# MainBoard_v1_2.net
KiCad netlist of a schematic drawn in EAGLE
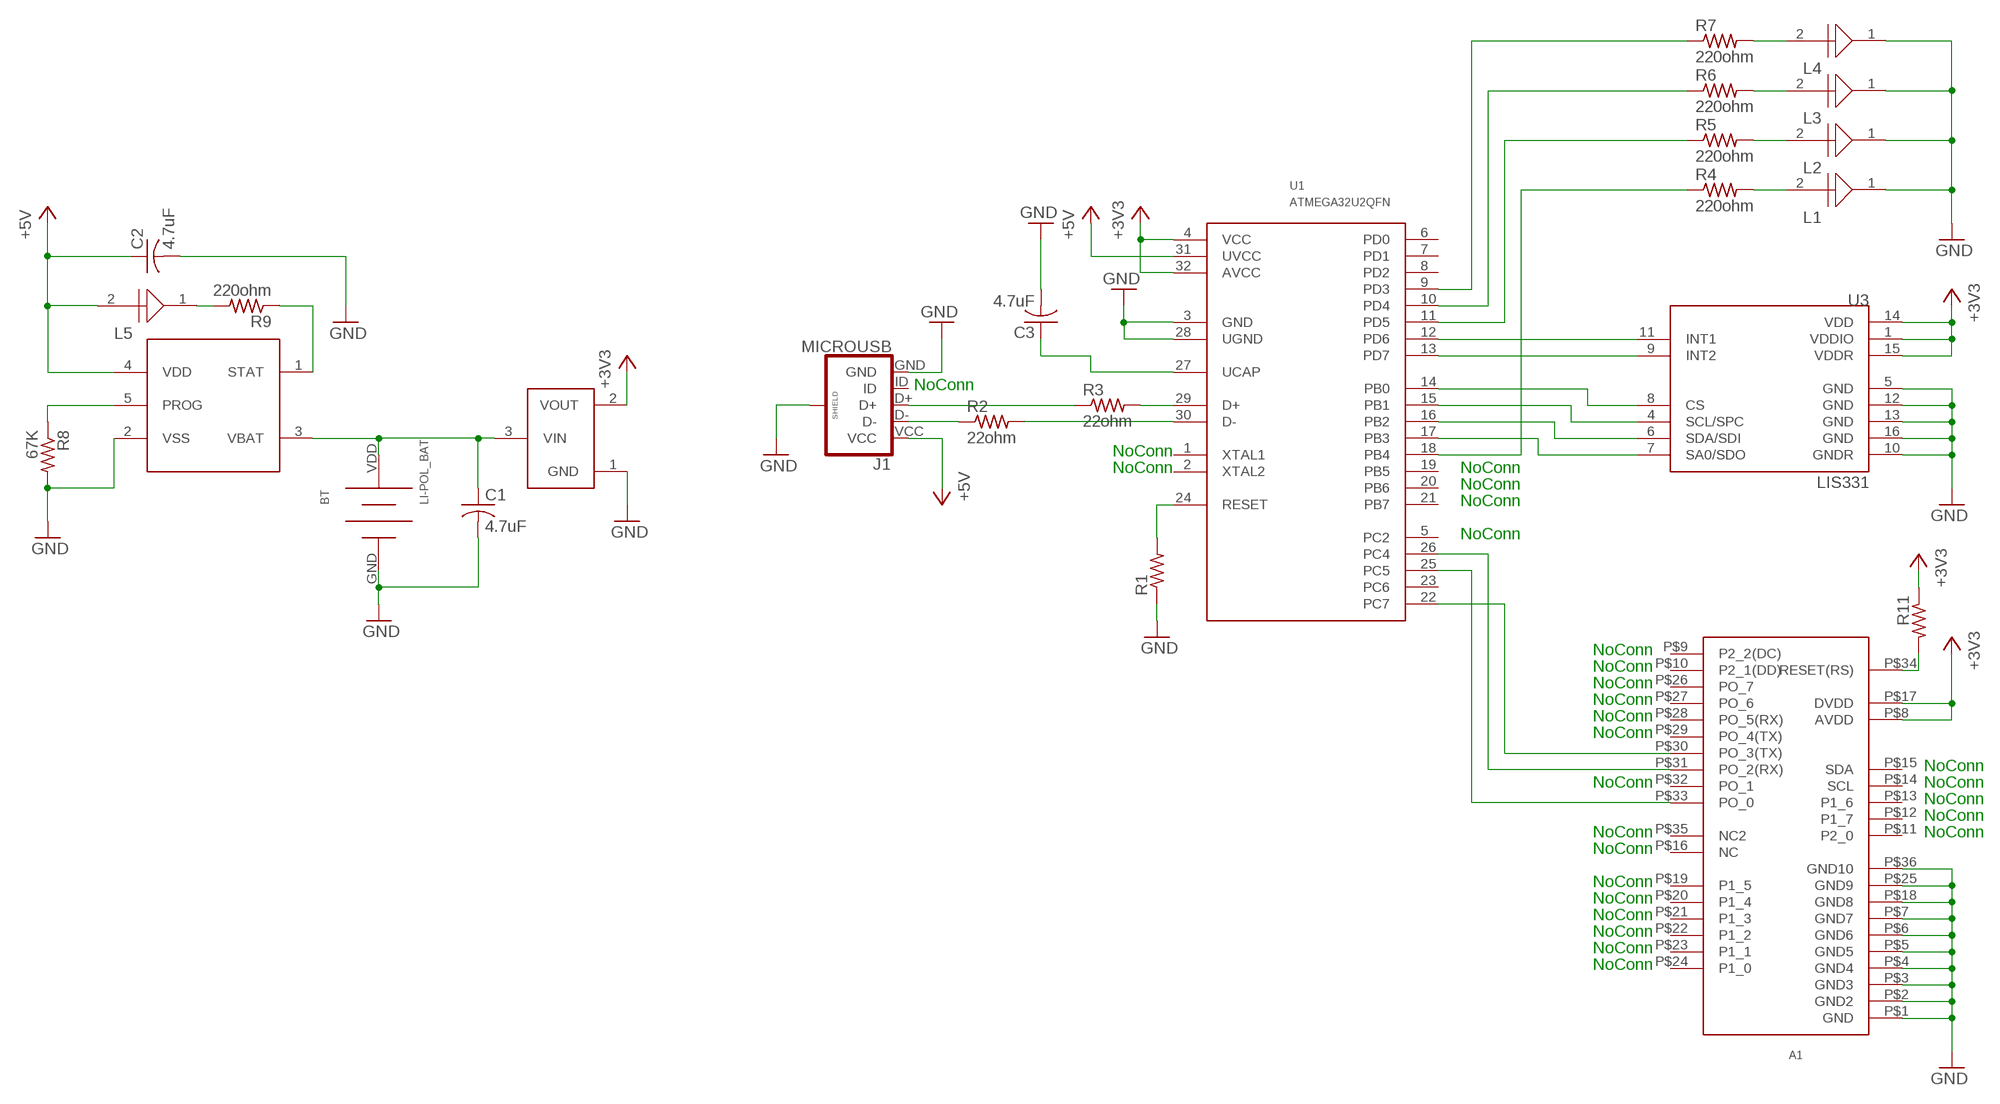
[diagram p0: schematic, sheet 1]

(export (version "E")
  (design (tool "Eeschema 10.0.6"))
  (components
    (comp (ref "A1")
      (value "BLE113-A")
      (footprint "eagle-import:BLUETOOTHNS")
      (libsource (lib "eagle-import") (part "BLE113-A"))
    )
    (comp (ref "BT")
      (value "LI-POL_BAT")
      (footprint "eagle-import:LI-POLY_28")
      (libsource (lib "eagle-import") (part "LI-POL_BAT"))
    )
    (comp (ref "C1")
      (value "4.7uF")
      (footprint "eagle-import:C0402")
      (libsource (lib "eagle-import") (part "C-USC0402"))
    )
    (comp (ref "C2")
      (value "4.7uF")
      (footprint "eagle-import:C0402")
      (libsource (lib "eagle-import") (part "C-USC0402"))
    )
    (comp (ref "C3")
      (value "4.7uF")
      (footprint "eagle-import:C0402")
      (libsource (lib "eagle-import") (part "C-USC0402"))
    )
    (comp (ref "J1")
      (value "MICROUSB")
      (footprint "eagle-import:MICROUSB")
      (libsource (lib "eagle-import") (part "MICROUSB"))
    )
    (comp (ref "L1")
      (value "LED_0402")
      (footprint "eagle-import:R0402")
      (libsource (lib "eagle-import") (part "LED_0402"))
    )
    (comp (ref "L2")
      (value "LED_0402")
      (footprint "eagle-import:R0402")
      (libsource (lib "eagle-import") (part "LED_0402"))
    )
    (comp (ref "L3")
      (value "LED_0402")
      (footprint "eagle-import:R0402")
      (libsource (lib "eagle-import") (part "LED_0402"))
    )
    (comp (ref "L4")
      (value "LED_0402")
      (footprint "eagle-import:R0402")
      (libsource (lib "eagle-import") (part "LED_0402"))
    )
    (comp (ref "L5")
      (value "LED_0402")
      (footprint "eagle-import:R0402")
      (libsource (lib "eagle-import") (part "LED_0402"))
    )
    (comp (ref "R1")
      (value "R-US_R0402")
      (footprint "eagle-import:R0402")
      (libsource (lib "eagle-import") (part "R-US_R0402"))
    )
    (comp (ref "R2")
      (value "22ohm")
      (footprint "eagle-import:R0402")
      (libsource (lib "eagle-import") (part "R-US_R0402"))
    )
    (comp (ref "R3")
      (value "22ohm")
      (footprint "eagle-import:R0402")
      (libsource (lib "eagle-import") (part "R-US_R0402"))
    )
    (comp (ref "R4")
      (value "220ohm")
      (footprint "eagle-import:R0402")
      (libsource (lib "eagle-import") (part "R-US_R0402"))
    )
    (comp (ref "R5")
      (value "220ohm")
      (footprint "eagle-import:R0402")
      (libsource (lib "eagle-import") (part "R-US_R0402"))
    )
    (comp (ref "R6")
      (value "220ohm")
      (footprint "eagle-import:R0402")
      (libsource (lib "eagle-import") (part "R-US_R0402"))
    )
    (comp (ref "R7")
      (value "220ohm")
      (footprint "eagle-import:R0402")
      (libsource (lib "eagle-import") (part "R-US_R0402"))
    )
    (comp (ref "R8")
      (value "67K")
      (footprint "eagle-import:R0402")
      (libsource (lib "eagle-import") (part "R-US_R0402"))
    )
    (comp (ref "R9")
      (value "220ohm")
      (footprint "eagle-import:R0402")
      (libsource (lib "eagle-import") (part "R-US_R0402"))
    )
    (comp (ref "R11")
      (value "R-US_R0402")
      (footprint "eagle-import:R0402")
      (libsource (lib "eagle-import") (part "R-US_R0402"))
    )
    (comp (ref "U1")
      (value "ATMEGA32U2QFN")
      (footprint "eagle-import:QFN-32")
      (libsource (lib "eagle-import") (part "ATMEGA32U2QFN"))
    )
    (comp (ref "U2")
      (value "MCP738312")
      (footprint "eagle-import:SOT23-5")
      (libsource (lib "eagle-import") (part "MCP738312"))
    )
    (comp (ref "U3")
      (value "LIS331")
      (footprint "eagle-import:LGA16-3MM")
      (libsource (lib "eagle-import") (part "LIS331"))
    )
    (comp (ref "U5")
      (value "REGULATOR")
      (footprint "eagle-import:SOT23-3")
      (libsource (lib "eagle-import") (part "REGULATOR"))
    )
  )
  (nets
    (net (code "1") (name "+3V3") (class "Default")
      (node (ref "A1") (pin "P$17") (pinfunction "DVDD_P$17") (pintype "bidirectional"))
      (node (ref "A1") (pin "P$8") (pinfunction "AVDD_P$8") (pintype "bidirectional"))
      (node (ref "R11") (pin "1") (pinfunction "1_1") (pintype "passive"))
      (node (ref "U1") (pin "32") (pinfunction "AVCC_32") (pintype "bidirectional"))
      (node (ref "U1") (pin "4") (pinfunction "VCC_4") (pintype "bidirectional"))
      (node (ref "U3") (pin "1") (pinfunction "VDDIO_1") (pintype "bidirectional"))
      (node (ref "U3") (pin "14") (pinfunction "VDD_14") (pintype "bidirectional"))
      (node (ref "U3") (pin "15") (pinfunction "VDDR_15") (pintype "bidirectional"))
      (node (ref "U5") (pin "2") (pinfunction "VOUT_2") (pintype "bidirectional"))
    )
    (net (code "2") (name "+5V") (class "Default")
      (node (ref "C2") (pin "1") (pinfunction "1_1") (pintype "passive"))
      (node (ref "J1") (pin "VCC") (pinfunction "VCC_VCC") (pintype "bidirectional"))
      (node (ref "L5") (pin "2") (pinfunction "P2_2") (pintype "bidirectional"))
      (node (ref "U1") (pin "31") (pinfunction "UVCC_31") (pintype "bidirectional"))
      (node (ref "U2") (pin "4") (pinfunction "VDD_4") (pintype "bidirectional"))
    )
    (net (code "3") (name "GND") (class "Default")
      (node (ref "A1") (pin "P$1") (pinfunction "GND_P$1") (pintype "bidirectional"))
      (node (ref "A1") (pin "P$18") (pinfunction "GND8_P$18") (pintype "bidirectional"))
      (node (ref "A1") (pin "P$2") (pinfunction "GND2_P$2") (pintype "bidirectional"))
      (node (ref "A1") (pin "P$25") (pinfunction "GND9_P$25") (pintype "bidirectional"))
      (node (ref "A1") (pin "P$3") (pinfunction "GND3_P$3") (pintype "bidirectional"))
      (node (ref "A1") (pin "P$36") (pinfunction "GND10_P$36") (pintype "bidirectional"))
      (node (ref "A1") (pin "P$4") (pinfunction "GND4_P$4") (pintype "bidirectional"))
      (node (ref "A1") (pin "P$5") (pinfunction "GND5_P$5") (pintype "bidirectional"))
      (node (ref "A1") (pin "P$6") (pinfunction "GND6_P$6") (pintype "bidirectional"))
      (node (ref "A1") (pin "P$7") (pinfunction "GND7_P$7") (pintype "bidirectional"))
      (node (ref "BT") (pin "GND") (pinfunction "GND_GND") (pintype "bidirectional"))
      (node (ref "C1") (pin "2") (pinfunction "2_2") (pintype "passive"))
      (node (ref "C2") (pin "2") (pinfunction "2_2") (pintype "passive"))
      (node (ref "C3") (pin "2") (pinfunction "2_2") (pintype "passive"))
      (node (ref "J1") (pin "GD1") (pinfunction "SHIELD_GD1") (pintype "bidirectional"))
      (node (ref "J1") (pin "GD2") (pinfunction "SHIELD_GD2") (pintype "bidirectional"))
      (node (ref "J1") (pin "GD3") (pinfunction "SHIELD_GD3") (pintype "bidirectional"))
      (node (ref "J1") (pin "GD4") (pinfunction "SHIELD_GD4") (pintype "bidirectional"))
      (node (ref "J1") (pin "GND") (pinfunction "GND_GND") (pintype "bidirectional"))
      (node (ref "L1") (pin "1") (pinfunction "P1_1") (pintype "bidirectional"))
      (node (ref "L2") (pin "1") (pinfunction "P1_1") (pintype "bidirectional"))
      (node (ref "L3") (pin "1") (pinfunction "P1_1") (pintype "bidirectional"))
      (node (ref "L4") (pin "1") (pinfunction "P1_1") (pintype "bidirectional"))
      (node (ref "R1") (pin "1") (pinfunction "1_1") (pintype "passive"))
      (node (ref "R8") (pin "2") (pinfunction "2_2") (pintype "passive"))
      (node (ref "U1") (pin "28") (pinfunction "UGND_28") (pintype "bidirectional"))
      (node (ref "U1") (pin "3") (pinfunction "GND_3") (pintype "bidirectional"))
      (node (ref "U2") (pin "2") (pinfunction "VSS_2") (pintype "bidirectional"))
      (node (ref "U3") (pin "10") (pinfunction "GNDR_10") (pintype "bidirectional"))
      (node (ref "U3") (pin "12") (pinfunction "GND_12") (pintype "bidirectional"))
      (node (ref "U3") (pin "13") (pinfunction "GND_13") (pintype "bidirectional"))
      (node (ref "U3") (pin "16") (pinfunction "GND_16") (pintype "bidirectional"))
      (node (ref "U3") (pin "5") (pinfunction "GND_5") (pintype "bidirectional"))
      (node (ref "U5") (pin "1") (pinfunction "GND_1") (pintype "bidirectional"))
    )
    (net (code "4") (name "Net-(A1-PO_0)") (class "Default")
      (node (ref "A1") (pin "P$33") (pinfunction "PO_0_P$33") (pintype "bidirectional"))
      (node (ref "U1") (pin "25") (pinfunction "PC5_25") (pintype "bidirectional"))
    )
    (net (code "5") (name "Net-(A1-PO_2(RX))") (class "Default")
      (node (ref "A1") (pin "P$31") (pinfunction "PO_2(RX)_P$31") (pintype "bidirectional"))
      (node (ref "U1") (pin "26") (pinfunction "PC4_26") (pintype "bidirectional"))
    )
    (net (code "6") (name "Net-(A1-PO_3(TX))") (class "Default")
      (node (ref "A1") (pin "P$30") (pinfunction "PO_3(TX)_P$30") (pintype "bidirectional"))
      (node (ref "U1") (pin "22") (pinfunction "PC7_22") (pintype "bidirectional"))
    )
    (net (code "7") (name "Net-(A1-RESET(RS))") (class "Default")
      (node (ref "A1") (pin "P$34") (pinfunction "RESET(RS)_P$34") (pintype "bidirectional"))
      (node (ref "R11") (pin "2") (pinfunction "2_2") (pintype "passive"))
    )
    (net (code "8") (name "Net-(J1-PadD+)") (class "Default")
      (node (ref "J1") (pin "D+") (pinfunction "D+_D+") (pintype "bidirectional"))
      (node (ref "R3") (pin "1") (pinfunction "1_1") (pintype "passive"))
    )
    (net (code "9") (name "Net-(J1-PadD-)") (class "Default")
      (node (ref "J1") (pin "D-") (pinfunction "D-_D-") (pintype "bidirectional"))
      (node (ref "R2") (pin "1") (pinfunction "1_1") (pintype "passive"))
    )
    (net (code "10") (name "Net-(L1-P2)") (class "Default")
      (node (ref "L1") (pin "2") (pinfunction "P2_2") (pintype "bidirectional"))
      (node (ref "R4") (pin "2") (pinfunction "2_2") (pintype "passive"))
    )
    (net (code "11") (name "Net-(L2-P2)") (class "Default")
      (node (ref "L2") (pin "2") (pinfunction "P2_2") (pintype "bidirectional"))
      (node (ref "R5") (pin "2") (pinfunction "2_2") (pintype "passive"))
    )
    (net (code "12") (name "Net-(L3-P2)") (class "Default")
      (node (ref "L3") (pin "2") (pinfunction "P2_2") (pintype "bidirectional"))
      (node (ref "R6") (pin "2") (pinfunction "2_2") (pintype "passive"))
    )
    (net (code "13") (name "Net-(L4-P2)") (class "Default")
      (node (ref "L4") (pin "2") (pinfunction "P2_2") (pintype "bidirectional"))
      (node (ref "R7") (pin "2") (pinfunction "2_2") (pintype "passive"))
    )
    (net (code "14") (name "Net-(L5-P1)") (class "Default")
      (node (ref "L5") (pin "1") (pinfunction "P1_1") (pintype "bidirectional"))
      (node (ref "R9") (pin "2") (pinfunction "2_2") (pintype "passive"))
    )
    (net (code "15") (name "Net-(U1-D+)") (class "Default")
      (node (ref "R3") (pin "2") (pinfunction "2_2") (pintype "passive"))
      (node (ref "U1") (pin "29") (pinfunction "D+_29") (pintype "bidirectional"))
    )
    (net (code "16") (name "Net-(U1-D-)") (class "Default")
      (node (ref "R2") (pin "2") (pinfunction "2_2") (pintype "passive"))
      (node (ref "U1") (pin "30") (pinfunction "D-_30") (pintype "bidirectional"))
    )
    (net (code "17") (name "Net-(U1-PB0)") (class "Default")
      (node (ref "U1") (pin "14") (pinfunction "PB0_14") (pintype "bidirectional"))
      (node (ref "U3") (pin "8") (pinfunction "CS_8") (pintype "bidirectional"))
    )
    (net (code "18") (name "Net-(U1-PB1)") (class "Default")
      (node (ref "U1") (pin "15") (pinfunction "PB1_15") (pintype "bidirectional"))
      (node (ref "U3") (pin "4") (pinfunction "SCL/SPC_4") (pintype "bidirectional"))
    )
    (net (code "19") (name "Net-(U1-PB2)") (class "Default")
      (node (ref "U1") (pin "16") (pinfunction "PB2_16") (pintype "bidirectional"))
      (node (ref "U3") (pin "6") (pinfunction "SDA/SDI_6") (pintype "bidirectional"))
    )
    (net (code "20") (name "Net-(U1-PB3)") (class "Default")
      (node (ref "U1") (pin "17") (pinfunction "PB3_17") (pintype "bidirectional"))
      (node (ref "U3") (pin "7") (pinfunction "SA0/SDO_7") (pintype "bidirectional"))
    )
    (net (code "21") (name "Net-(U1-PB4)") (class "Default")
      (node (ref "R4") (pin "1") (pinfunction "1_1") (pintype "passive"))
      (node (ref "U1") (pin "18") (pinfunction "PB4_18") (pintype "bidirectional"))
    )
    (net (code "22") (name "Net-(U1-PD3)") (class "Default")
      (node (ref "R7") (pin "1") (pinfunction "1_1") (pintype "passive"))
      (node (ref "U1") (pin "9") (pinfunction "PD3_9") (pintype "bidirectional"))
    )
    (net (code "23") (name "Net-(U1-PD4)") (class "Default")
      (node (ref "R6") (pin "1") (pinfunction "1_1") (pintype "passive"))
      (node (ref "U1") (pin "10") (pinfunction "PD4_10") (pintype "bidirectional"))
    )
    (net (code "24") (name "Net-(U1-PD5)") (class "Default")
      (node (ref "R5") (pin "1") (pinfunction "1_1") (pintype "passive"))
      (node (ref "U1") (pin "11") (pinfunction "PD5_11") (pintype "bidirectional"))
    )
    (net (code "25") (name "Net-(U1-PD6)") (class "Default")
      (node (ref "U1") (pin "12") (pinfunction "PD6_12") (pintype "bidirectional"))
      (node (ref "U3") (pin "11") (pinfunction "INT1_11") (pintype "bidirectional"))
    )
    (net (code "26") (name "Net-(U1-PD7)") (class "Default")
      (node (ref "U1") (pin "13") (pinfunction "PD7_13") (pintype "bidirectional"))
      (node (ref "U3") (pin "9") (pinfunction "INT2_9") (pintype "bidirectional"))
    )
    (net (code "27") (name "Net-(U1-RESET)") (class "Default")
      (node (ref "R1") (pin "2") (pinfunction "2_2") (pintype "passive"))
      (node (ref "U1") (pin "24") (pinfunction "RESET_24") (pintype "bidirectional"))
    )
    (net (code "28") (name "Net-(U1-UCAP)") (class "Default")
      (node (ref "C3") (pin "1") (pinfunction "1_1") (pintype "passive"))
      (node (ref "U1") (pin "27") (pinfunction "UCAP_27") (pintype "bidirectional"))
    )
    (net (code "29") (name "Net-(U2-PROG)") (class "Default")
      (node (ref "R8") (pin "1") (pinfunction "1_1") (pintype "passive"))
      (node (ref "U2") (pin "5") (pinfunction "PROG_5") (pintype "bidirectional"))
    )
    (net (code "30") (name "Net-(U2-STAT)") (class "Default")
      (node (ref "R9") (pin "1") (pinfunction "1_1") (pintype "passive"))
      (node (ref "U2") (pin "1") (pinfunction "STAT_1") (pintype "bidirectional"))
    )
    (net (code "31") (name "Net-(U2-VBAT)") (class "Default")
      (node (ref "BT") (pin "VDD") (pinfunction "VDD_VDD") (pintype "bidirectional"))
      (node (ref "C1") (pin "1") (pinfunction "1_1") (pintype "passive"))
      (node (ref "U2") (pin "3") (pinfunction "VBAT_3") (pintype "bidirectional"))
      (node (ref "U5") (pin "3") (pinfunction "VIN_3") (pintype "bidirectional"))
    )
    (net (code "32") (name "unconnected-(A1-NC-PadP$16)") (class "Default")
      (node (ref "A1") (pin "P$16") (pinfunction "NC_P$16") (pintype "bidirectional"))
    )
    (net (code "33") (name "unconnected-(A1-NC2-PadP$35)") (class "Default")
      (node (ref "A1") (pin "P$35") (pinfunction "NC2_P$35") (pintype "bidirectional"))
    )
    (net (code "34") (name "unconnected-(A1-P1_0-PadP$24)") (class "Default")
      (node (ref "A1") (pin "P$24") (pinfunction "P1_0_P$24") (pintype "bidirectional"))
    )
    (net (code "35") (name "unconnected-(A1-P1_1-PadP$23)") (class "Default")
      (node (ref "A1") (pin "P$23") (pinfunction "P1_1_P$23") (pintype "bidirectional"))
    )
    (net (code "36") (name "unconnected-(A1-P1_2-PadP$22)") (class "Default")
      (node (ref "A1") (pin "P$22") (pinfunction "P1_2_P$22") (pintype "bidirectional"))
    )
    (net (code "37") (name "unconnected-(A1-P1_3-PadP$21)") (class "Default")
      (node (ref "A1") (pin "P$21") (pinfunction "P1_3_P$21") (pintype "bidirectional"))
    )
    (net (code "38") (name "unconnected-(A1-P1_4-PadP$20)") (class "Default")
      (node (ref "A1") (pin "P$20") (pinfunction "P1_4_P$20") (pintype "bidirectional"))
    )
    (net (code "39") (name "unconnected-(A1-P1_5-PadP$19)") (class "Default")
      (node (ref "A1") (pin "P$19") (pinfunction "P1_5_P$19") (pintype "bidirectional"))
    )
    (net (code "40") (name "unconnected-(A1-P1_6-PadP$13)") (class "Default")
      (node (ref "A1") (pin "P$13") (pinfunction "P1_6_P$13") (pintype "bidirectional"))
    )
    (net (code "41") (name "unconnected-(A1-P1_7-PadP$12)") (class "Default")
      (node (ref "A1") (pin "P$12") (pinfunction "P1_7_P$12") (pintype "bidirectional"))
    )
    (net (code "42") (name "unconnected-(A1-P2_0-PadP$11)") (class "Default")
      (node (ref "A1") (pin "P$11") (pinfunction "P2_0_P$11") (pintype "bidirectional"))
    )
    (net (code "43") (name "unconnected-(A1-P2_1(DD)-PadP$10)") (class "Default")
      (node (ref "A1") (pin "P$10") (pinfunction "P2_1(DD)_P$10") (pintype "bidirectional"))
    )
    (net (code "44") (name "unconnected-(A1-P2_2(DC)-PadP$9)") (class "Default")
      (node (ref "A1") (pin "P$9") (pinfunction "P2_2(DC)_P$9") (pintype "bidirectional"))
    )
    (net (code "45") (name "unconnected-(A1-PO_1-PadP$32)") (class "Default")
      (node (ref "A1") (pin "P$32") (pinfunction "PO_1_P$32") (pintype "bidirectional"))
    )
    (net (code "46") (name "unconnected-(A1-PO_4(TX)-PadP$29)") (class "Default")
      (node (ref "A1") (pin "P$29") (pinfunction "PO_4(TX)_P$29") (pintype "bidirectional"))
    )
    (net (code "47") (name "unconnected-(A1-PO_5(RX)-PadP$28)") (class "Default")
      (node (ref "A1") (pin "P$28") (pinfunction "PO_5(RX)_P$28") (pintype "bidirectional"))
    )
    (net (code "48") (name "unconnected-(A1-PO_6-PadP$27)") (class "Default")
      (node (ref "A1") (pin "P$27") (pinfunction "PO_6_P$27") (pintype "bidirectional"))
    )
    (net (code "49") (name "unconnected-(A1-PO_7-PadP$26)") (class "Default")
      (node (ref "A1") (pin "P$26") (pinfunction "PO_7_P$26") (pintype "bidirectional"))
    )
    (net (code "50") (name "unconnected-(A1-SCL-PadP$14)") (class "Default")
      (node (ref "A1") (pin "P$14") (pinfunction "SCL_P$14") (pintype "bidirectional"))
    )
    (net (code "51") (name "unconnected-(A1-SDA-PadP$15)") (class "Default")
      (node (ref "A1") (pin "P$15") (pinfunction "SDA_P$15") (pintype "bidirectional"))
    )
    (net (code "52") (name "unconnected-(J1-PadID)") (class "Default")
      (node (ref "J1") (pin "ID") (pinfunction "ID_ID") (pintype "bidirectional"))
    )
    (net (code "53") (name "unconnected-(U1-PB5-Pad19)") (class "Default")
      (node (ref "U1") (pin "19") (pinfunction "PB5_19") (pintype "bidirectional"))
    )
    (net (code "54") (name "unconnected-(U1-PB6-Pad20)") (class "Default")
      (node (ref "U1") (pin "20") (pinfunction "PB6_20") (pintype "bidirectional"))
    )
    (net (code "55") (name "unconnected-(U1-PB7-Pad21)") (class "Default")
      (node (ref "U1") (pin "21") (pinfunction "PB7_21") (pintype "bidirectional"))
    )
    (net (code "56") (name "unconnected-(U1-PC2-Pad5)") (class "Default")
      (node (ref "U1") (pin "5") (pinfunction "PC2_5") (pintype "bidirectional"))
    )
    (net (code "57") (name "unconnected-(U1-PC6-Pad23)") (class "Default")
      (node (ref "U1") (pin "23") (pinfunction "PC6_23") (pintype "bidirectional"))
    )
    (net (code "58") (name "unconnected-(U1-PD0-Pad6)") (class "Default")
      (node (ref "U1") (pin "6") (pinfunction "PD0_6") (pintype "bidirectional"))
    )
    (net (code "59") (name "unconnected-(U1-PD1-Pad7)") (class "Default")
      (node (ref "U1") (pin "7") (pinfunction "PD1_7") (pintype "bidirectional"))
    )
    (net (code "60") (name "unconnected-(U1-PD2-Pad8)") (class "Default")
      (node (ref "U1") (pin "8") (pinfunction "PD2_8") (pintype "bidirectional"))
    )
    (net (code "61") (name "unconnected-(U1-XTAL1-Pad1)") (class "Default")
      (node (ref "U1") (pin "1") (pinfunction "XTAL1_1") (pintype "bidirectional"))
    )
    (net (code "62") (name "unconnected-(U1-XTAL2-Pad2)") (class "Default")
      (node (ref "U1") (pin "2") (pinfunction "XTAL2_2") (pintype "bidirectional"))
    )
  )
)
